# schem.net
KiCad netlist of a schematic drawn in EasyEDA
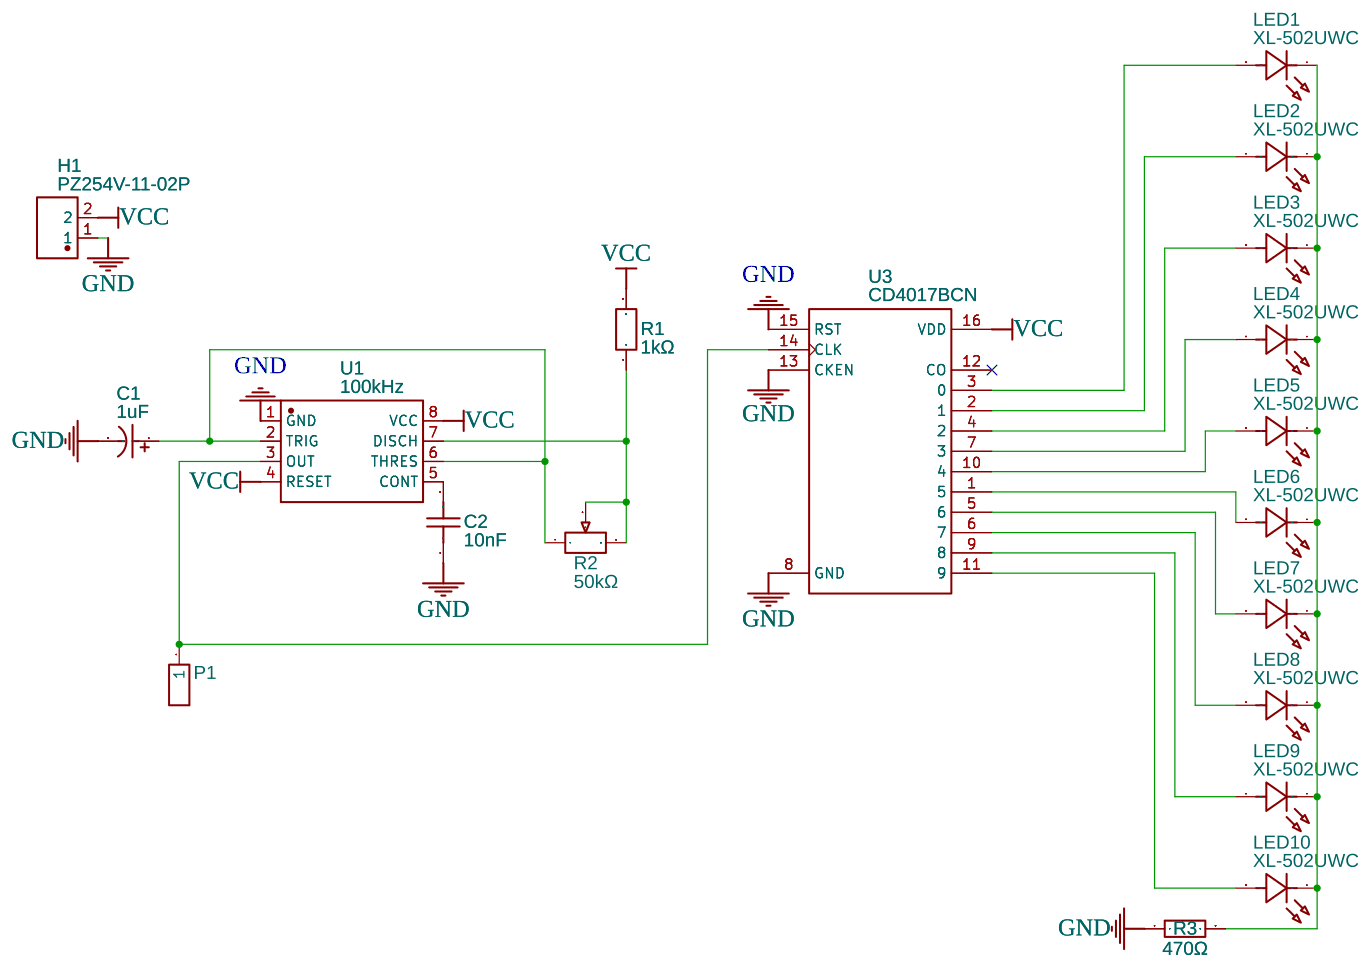
[diagram p0: schematic sheet]

(export (version "E")
  (design (tool "Eeschema 10.0.6"))
  (components
    (comp (ref "C1")
      (value "1uF")
      (fields (field (name "Manufacturer Part") "KF010M050C110A") (field (name "Manufacturer") "CapXon(丰宾)"))
      (libsource (lib "") (part "KF010M050C110A"))
    )
    (comp (ref "C2")
      (value "10nF")
      (fields (field (name "Manufacturer Part") "N09F1B103MN0B0S0N0") (field (name "Manufacturer") "STE(松田)"))
      (libsource (lib "") (part "N09F1B103MN0B0S0N0"))
    )
    (comp (ref "H1")
      (value "PZ254V-11-02P")
      (fields (field (name "Manufacturer") "XFCN(兴飞)"))
      (libsource (lib "") (part "PZ254V-11-02P"))
    )
    (comp (ref "LED1")
      (value "XL-502UWC")
      (fields (field (name "Manufacturer") "XINGLIGHT(成兴光)"))
      (libsource (lib "") (part "XL-502UWC"))
    )
    (comp (ref "LED2")
      (value "XL-502UWC")
      (fields (field (name "Manufacturer") "XINGLIGHT(成兴光)"))
      (libsource (lib "") (part "XL-502UWC"))
    )
    (comp (ref "LED3")
      (value "XL-502UWC")
      (fields (field (name "Manufacturer") "XINGLIGHT(成兴光)"))
      (libsource (lib "") (part "XL-502UWC"))
    )
    (comp (ref "LED4")
      (value "XL-502UWC")
      (fields (field (name "Manufacturer") "XINGLIGHT(成兴光)"))
      (libsource (lib "") (part "XL-502UWC"))
    )
    (comp (ref "LED5")
      (value "XL-502UWC")
      (fields (field (name "Manufacturer") "XINGLIGHT(成兴光)"))
      (libsource (lib "") (part "XL-502UWC"))
    )
    (comp (ref "LED6")
      (value "XL-502UWC")
      (fields (field (name "Manufacturer") "XINGLIGHT(成兴光)"))
      (libsource (lib "") (part "XL-502UWC"))
    )
    (comp (ref "LED7")
      (value "XL-502UWC")
      (fields (field (name "Manufacturer") "XINGLIGHT(成兴光)"))
      (libsource (lib "") (part "XL-502UWC"))
    )
    (comp (ref "LED8")
      (value "XL-502UWC")
      (fields (field (name "Manufacturer") "XINGLIGHT(成兴光)"))
      (libsource (lib "") (part "XL-502UWC"))
    )
    (comp (ref "LED9")
      (value "XL-502UWC")
      (fields (field (name "Manufacturer") "XINGLIGHT(成兴光)"))
      (libsource (lib "") (part "XL-502UWC"))
    )
    (comp (ref "LED10")
      (value "XL-502UWC")
      (fields (field (name "Manufacturer") "XINGLIGHT(成兴光)"))
      (libsource (lib "") (part "XL-502UWC"))
    )
    (comp (ref "P1")
      (value "Header-Male-2.54_1x1")
      (fields (field (name "Manufacturer Part") "2.54-1*1P针") (field (name "Manufacturer") "BOOMELE(博穆精密)"))
      (libsource (lib "") (part "Header-Male-2.54_1x1"))
    )
    (comp (ref "R1")
      (value "1kΩ")
      (fields (field (name "Manufacturer Part") "MF1/4W-1KΩ±1%T52") (field (name "Manufacturer") "华星机电"))
      (libsource (lib "") (part "MF1/4W-1KΩ±1%T52"))
    )
    (comp (ref "R2")
      (value "50kΩ")
      (fields (field (name "Manufacturer Part") "3296X-1-503") (field (name "Manufacturer") "BOCHEN(博晨)"))
      (libsource (lib "") (part "3296X-1-503_C118912"))
    )
    (comp (ref "R3")
      (value "470Ω")
      (fields
        (field (name "Manufacturer Part") "MFR0W4F4700A50")
        (field (name "Manufacturer") "UNI-ROYAL(厚声)")
      )
      (libsource (lib "") (part "MFR0W4F4700A50"))
    )
    (comp (ref "U1")
      (value "100kHz")
      (fields (field (name "Manufacturer Part") "NE555P") (field (name "Manufacturer") "TI(德州仪器)"))
      (libsource (lib "") (part "NE555P"))
    )
    (comp (ref "U3") (value "CD4017BCN") (libsource (lib "") (part "CD4017BCN")))
  )
  (nets
    (net (code "1") (name "GND") (class "Default")
      (node (ref "C1") (pin "2") (pinfunction "2_2") (pintype "input"))
      (node (ref "C2") (pin "1") (pinfunction "1_1") (pintype "unspecified"))
      (node (ref "H1") (pin "1") (pinfunction "1_1") (pintype "unspecified"))
      (node (ref "R3") (pin "1") (pinfunction "1_1") (pintype "input"))
      (node (ref "U1") (pin "1") (pinfunction "GND_1") (pintype "unspecified"))
      (node (ref "U3") (pin "13") (pinfunction "CKEN_13") (pintype "unspecified"))
      (node (ref "U3") (pin "15") (pinfunction "RST_15") (pintype "unspecified"))
      (node (ref "U3") (pin "8") (pinfunction "GND_8") (pintype "passive"))
    )
    (net (code "2") (name "Net-(LED1-A)") (class "Default")
      (node (ref "LED1") (pin "2") (pinfunction "A_2") (pintype "unspecified"))
      (node (ref "U3") (pin "3") (pinfunction "0_3") (pintype "output"))
    )
    (net (code "3") (name "Net-(LED1-K)") (class "Default")
      (node (ref "LED1") (pin "1") (pinfunction "K_1") (pintype "unspecified"))
      (node (ref "LED10") (pin "1") (pinfunction "K_1") (pintype "unspecified"))
      (node (ref "LED2") (pin "1") (pinfunction "K_1") (pintype "unspecified"))
      (node (ref "LED3") (pin "1") (pinfunction "K_1") (pintype "unspecified"))
      (node (ref "LED4") (pin "1") (pinfunction "K_1") (pintype "unspecified"))
      (node (ref "LED5") (pin "1") (pinfunction "K_1") (pintype "unspecified"))
      (node (ref "LED6") (pin "1") (pinfunction "K_1") (pintype "unspecified"))
      (node (ref "LED7") (pin "1") (pinfunction "K_1") (pintype "unspecified"))
      (node (ref "LED8") (pin "1") (pinfunction "K_1") (pintype "unspecified"))
      (node (ref "LED9") (pin "1") (pinfunction "K_1") (pintype "unspecified"))
      (node (ref "R3") (pin "2") (pinfunction "2_2") (pintype "input"))
    )
    (net (code "4") (name "Net-(LED2-A)") (class "Default")
      (node (ref "LED2") (pin "2") (pinfunction "A_2") (pintype "unspecified"))
      (node (ref "U3") (pin "2") (pinfunction "1_2") (pintype "output"))
    )
    (net (code "5") (name "Net-(LED3-A)") (class "Default")
      (node (ref "LED3") (pin "2") (pinfunction "A_2") (pintype "unspecified"))
      (node (ref "U3") (pin "4") (pinfunction "2_4") (pintype "output"))
    )
    (net (code "6") (name "Net-(LED4-A)") (class "Default")
      (node (ref "LED4") (pin "2") (pinfunction "A_2") (pintype "unspecified"))
      (node (ref "U3") (pin "7") (pinfunction "3_7") (pintype "output"))
    )
    (net (code "7") (name "Net-(LED5-A)") (class "Default")
      (node (ref "LED5") (pin "2") (pinfunction "A_2") (pintype "unspecified"))
      (node (ref "U3") (pin "10") (pinfunction "4_10") (pintype "output"))
    )
    (net (code "8") (name "Net-(LED6-A)") (class "Default")
      (node (ref "LED6") (pin "2") (pinfunction "A_2") (pintype "unspecified"))
      (node (ref "U3") (pin "1") (pinfunction "5_1") (pintype "output"))
    )
    (net (code "9") (name "Net-(LED7-A)") (class "Default")
      (node (ref "LED7") (pin "2") (pinfunction "A_2") (pintype "unspecified"))
      (node (ref "U3") (pin "5") (pinfunction "6_5") (pintype "output"))
    )
    (net (code "10") (name "Net-(LED8-A)") (class "Default")
      (node (ref "LED8") (pin "2") (pinfunction "A_2") (pintype "unspecified"))
      (node (ref "U3") (pin "6") (pinfunction "7_6") (pintype "output"))
    )
    (net (code "11") (name "Net-(LED9-A)") (class "Default")
      (node (ref "LED9") (pin "2") (pinfunction "A_2") (pintype "unspecified"))
      (node (ref "U3") (pin "9") (pinfunction "8_9") (pintype "output"))
    )
    (net (code "12") (name "Net-(LED10-A)") (class "Default")
      (node (ref "LED10") (pin "2") (pinfunction "A_2") (pintype "unspecified"))
      (node (ref "U3") (pin "11") (pinfunction "9_11") (pintype "output"))
    )
    (net (code "13") (name "Net-(U1-CONT)") (class "Default")
      (node (ref "C2") (pin "2") (pinfunction "2_2") (pintype "unspecified"))
      (node (ref "U1") (pin "5") (pinfunction "CONT_5") (pintype "unspecified"))
    )
    (net (code "14") (name "Net-(U1-DISCH)") (class "Default")
      (node (ref "R1") (pin "1") (pinfunction "1_1") (pintype "unspecified"))
      (node (ref "R2") (pin "2") (pinfunction "2_2") (pintype "input"))
      (node (ref "R2") (pin "3") (pinfunction "3_3") (pintype "input"))
      (node (ref "U1") (pin "7") (pinfunction "DISCH_7") (pintype "unspecified"))
    )
    (net (code "15") (name "Net-(U1-OUT)") (class "Default")
      (node (ref "P1") (pin "1") (pinfunction "1_1") (pintype "input"))
      (node (ref "U1") (pin "3") (pinfunction "OUT_3") (pintype "unspecified"))
      (node (ref "U3") (pin "14") (pinfunction "CLK_14") (pintype "unspecified"))
    )
    (net (code "16") (name "Net-(U1-THRES)") (class "Default")
      (node (ref "C1") (pin "1") (pinfunction "1_1") (pintype "input"))
      (node (ref "R2") (pin "1") (pinfunction "1_1") (pintype "input"))
      (node (ref "U1") (pin "2") (pinfunction "TRIG_2") (pintype "unspecified"))
      (node (ref "U1") (pin "6") (pinfunction "THRES_6") (pintype "unspecified"))
    )
    (net (code "17") (name "VCC") (class "Default")
      (node (ref "H1") (pin "2") (pinfunction "2_2") (pintype "unspecified"))
      (node (ref "R1") (pin "2") (pinfunction "2_2") (pintype "unspecified"))
      (node (ref "U1") (pin "4") (pinfunction "RESET_4") (pintype "unspecified"))
      (node (ref "U1") (pin "8") (pinfunction "VCC_8") (pintype "unspecified"))
      (node (ref "U3") (pin "16") (pinfunction "VDD_16") (pintype "passive"))
    )
    (net (code "18") (name "unconnected-(U3-CO-Pad12)") (class "Default")
      (node (ref "U3") (pin "12") (pinfunction "CO_12") (pintype "output+no_connect"))
    )
  )
)
